# main.net
KiCad netlist of a schematic drawn in EAGLE
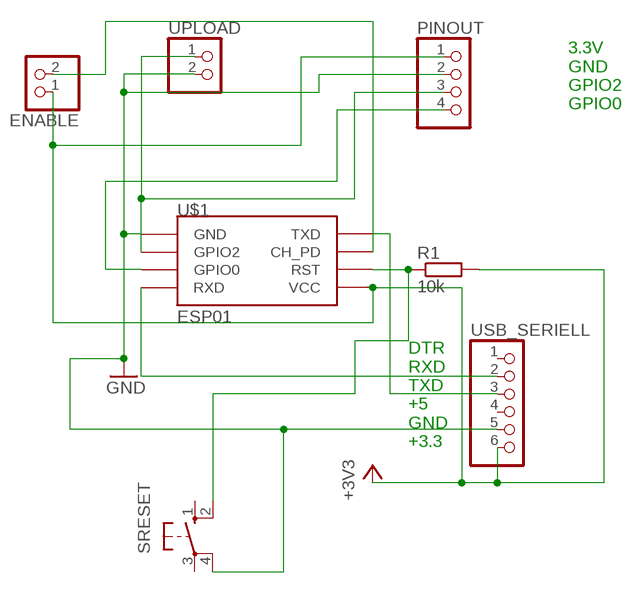
[diagram p0: schematic, sheet 1]

(export (version "E")
  (design (tool "Eeschema 10.0.6"))
  (components
    (comp (ref "ENABLE")
      (value "PINHD-1X2")
      (footprint "eagle-import:1X02")
      (libsource (lib "eagle-import") (part "PINHD-1X2"))
    )
    (comp (ref "PINOUT")
      (value "PINHD-1X4")
      (footprint "eagle-import:1X04")
      (libsource (lib "eagle-import") (part "PINHD-1X4"))
    )
    (comp (ref "R1")
      (value "10k")
      (footprint "eagle-import:0207_10")
      (libsource (lib "eagle-import") (part "R-EU_0207/10"))
    )
    (comp (ref "SRESET")
      (value "10-XX")
      (footprint "eagle-import:B3F-10XX")
      (fields (field (name "MPN") "B3F-1000"))
      (libsource (lib "eagle-import") (part "10-XX"))
    )
    (comp (ref "U$1")
      (value "ESP01")
      (footprint "eagle-import:ESP01")
      (libsource (lib "eagle-import") (part "ESP01"))
    )
    (comp (ref "UPLOAD")
      (value "PINHD-1X2")
      (footprint "eagle-import:1X02")
      (libsource (lib "eagle-import") (part "PINHD-1X2"))
    )
    (comp (ref "USB_SERIELL")
      (value "PINHD-1X6")
      (footprint "eagle-import:1X06")
      (libsource (lib "eagle-import") (part "PINHD-1X6"))
    )
  )
  (nets
    (net (code "1") (name "+3V3") (class "Default")
      (node (ref "ENABLE") (pin "1") (pinfunction "1_1") (pintype "passive"))
      (node (ref "PINOUT") (pin "1") (pinfunction "1_1") (pintype "passive"))
      (node (ref "R1") (pin "2") (pinfunction "2_2") (pintype "passive"))
      (node (ref "U$1") (pin "VCC") (pinfunction "VCC_VCC") (pintype "bidirectional"))
      (node (ref "USB_SERIELL") (pin "6") (pinfunction "6_6") (pintype "passive"))
    )
    (net (code "2") (name "GND") (class "Default")
      (node (ref "PINOUT") (pin "2") (pinfunction "2_2") (pintype "passive"))
      (node (ref "SRESET") (pin "4") (pinfunction "P1_4") (pintype "passive"))
      (node (ref "U$1") (pin "GND") (pinfunction "GND_GND") (pintype "bidirectional"))
      (node (ref "UPLOAD") (pin "2") (pinfunction "2_2") (pintype "passive"))
      (node (ref "USB_SERIELL") (pin "5") (pinfunction "5_5") (pintype "passive"))
    )
    (net (code "3") (name "Net-(ENABLE-Pad2)") (class "Default")
      (node (ref "ENABLE") (pin "2") (pinfunction "2_2") (pintype "passive"))
      (node (ref "U$1") (pin "CH_PD") (pinfunction "CH_PD_CH_PD") (pintype "bidirectional"))
    )
    (net (code "4") (name "Net-(PINOUT-Pad3)") (class "Default")
      (node (ref "PINOUT") (pin "3") (pinfunction "3_3") (pintype "passive"))
      (node (ref "U$1") (pin "GPIO2") (pinfunction "GPIO2_GPIO2") (pintype "bidirectional"))
      (node (ref "UPLOAD") (pin "1") (pinfunction "1_1") (pintype "passive"))
    )
    (net (code "5") (name "Net-(PINOUT-Pad4)") (class "Default")
      (node (ref "PINOUT") (pin "4") (pinfunction "4_4") (pintype "passive"))
      (node (ref "U$1") (pin "GPIO0") (pinfunction "GPIO0_GPIO0") (pintype "bidirectional"))
    )
    (net (code "6") (name "Net-(SRESET-S1)") (class "Default")
      (node (ref "R1") (pin "1") (pinfunction "1_1") (pintype "passive"))
      (node (ref "SRESET") (pin "2") (pinfunction "S1_2") (pintype "passive"))
      (node (ref "U$1") (pin "RST") (pinfunction "RST_RST") (pintype "bidirectional"))
    )
    (net (code "7") (name "Net-(U$1-RXD)") (class "Default")
      (node (ref "U$1") (pin "RX") (pinfunction "RXD_RX") (pintype "bidirectional"))
      (node (ref "USB_SERIELL") (pin "2") (pinfunction "2_2") (pintype "passive"))
    )
    (net (code "8") (name "Net-(U$1-TXD)") (class "Default")
      (node (ref "U$1") (pin "TX") (pinfunction "TXD_TX") (pintype "bidirectional"))
      (node (ref "USB_SERIELL") (pin "3") (pinfunction "3_3") (pintype "passive"))
    )
    (net (code "9") (name "unconnected-(SRESET-P-Pad3)") (class "Default")
      (node (ref "SRESET") (pin "3") (pinfunction "P_3") (pintype "passive"))
    )
    (net (code "10") (name "unconnected-(SRESET-S-Pad1)") (class "Default")
      (node (ref "SRESET") (pin "1") (pinfunction "S_1") (pintype "passive"))
    )
    (net (code "11") (name "unconnected-(USB_SERIELL-Pad1)") (class "Default")
      (node (ref "USB_SERIELL") (pin "1") (pinfunction "1_1") (pintype "passive"))
    )
    (net (code "12") (name "unconnected-(USB_SERIELL-Pad4)") (class "Default")
      (node (ref "USB_SERIELL") (pin "4") (pinfunction "4_4") (pintype "passive"))
    )
  )
)
